# References.net
KiCad netlist of a schematic drawn in Altium Designer
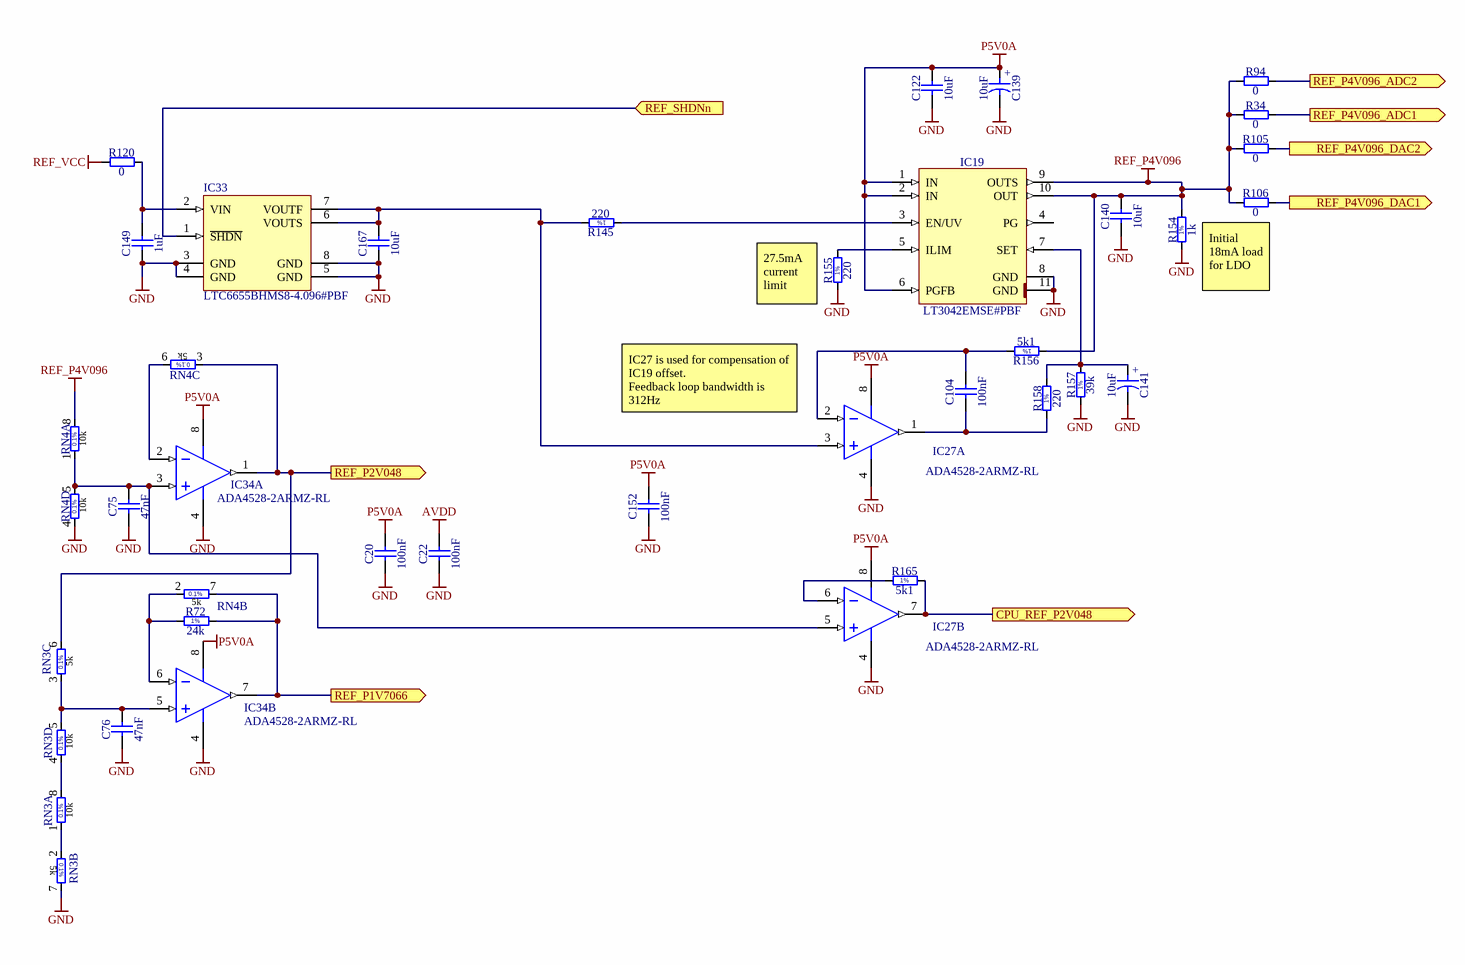
[diagram p0: References.SchDoc]

(export (version "E")
  (design (tool "Eeschema 10.0.6"))
  (components
    (comp (ref "C20")
      (value "100nF")
      (footprint "CAPC1005X55N")
      (description "Non-polarised capacitor")
      (fields
        (field (name "PART NUMBER") "CC0402_100NF_16V_10%_X5R")
        (field (name "VOLTAGE") "16V")
        (field (name "AUTHOR") "CERN DEM JLC")
      )
      (libsource (lib "Capacitors") (part "Capacitor - non polarized"))
    )
    (comp (ref "C22")
      (value "100nF")
      (footprint "CAPC1005X55N")
      (description "Non-polarised capacitor")
      (fields
        (field (name "PART NUMBER") "CC0402_100NF_16V_10%_X5R")
        (field (name "VOLTAGE") "16V")
        (field (name "AUTHOR") "CERN DEM JLC")
      )
      (libsource (lib "Capacitors") (part "Capacitor - non polarized"))
    )
    (comp (ref "C75")
      (value "47nF")
      (footprint "CAPC2012X135N")
      (description "Non-polarised capacitor")
      (fields
        (field (name "PART NUMBER") "CC0805_47NF_25V_5%_C0G")
        (field (name "VOLTAGE") "25V")
        (field (name "AUTHOR") "CERN DEM JLC")
      )
      (libsource (lib "Capacitors") (part "Capacitor - non polarized"))
    )
    (comp (ref "C76")
      (value "47nF")
      (footprint "CAPC2012X135N")
      (description "Non-polarised capacitor")
      (fields
        (field (name "PART NUMBER") "CC0805_47NF_25V_5%_C0G")
        (field (name "VOLTAGE") "25V")
        (field (name "AUTHOR") "CERN DEM JLC")
      )
      (libsource (lib "Capacitors") (part "Capacitor - non polarized"))
    )
    (comp (ref "C104")
      (value "100nF")
      (footprint "CAPC1005X55N")
      (description "Non-polarised capacitor")
      (fields
        (field (name "PART NUMBER") "CC0402_100NF_16V_10%_X5R")
        (field (name "VOLTAGE") "16V")
        (field (name "AUTHOR") "CERN DEM JLC")
      )
      (libsource (lib "Capacitors") (part "Capacitor - non polarized"))
    )
    (comp (ref "C122")
      (value "10uF")
      (footprint "CAPC1608X80N")
      (description "Non-polarised capacitor")
      (fields
        (field (name "PART NUMBER") "CC0603_10UF_10V_10%_X5R")
        (field (name "VOLTAGE") "10V")
        (field (name "AUTHOR") "CERN DEM JLC")
      )
      (libsource (lib "Capacitors") (part "Capacitor - non polarized"))
    )
    (comp (ref "C139")
      (value "10uF")
      (footprint "CAPMP3216X180N")
      (description "Polarised capacitor")
      (fields
        (field (name "PART NUMBER") "CTE3216-18_10UF_16V_20%_AVX_TCJ")
        (field (name "VOLTAGE") "16V")
        (field (name "AUTHOR") "CERN DEM JLC")
      )
      (libsource (lib "Capacitors") (part "Capacitor - polarized"))
    )
    (comp (ref "C140")
      (value "10uF")
      (footprint "CAPC1608X80N")
      (description "Non-polarised capacitor")
      (fields
        (field (name "PART NUMBER") "CC0603_10UF_10V_10%_X5R")
        (field (name "VOLTAGE") "10V")
        (field (name "AUTHOR") "CERN DEM JLC")
      )
      (libsource (lib "Capacitors") (part "Capacitor - non polarized"))
    )
    (comp (ref "C141")
      (value "10uF")
      (footprint "CAPMP3216X180N")
      (description "Polarised capacitor")
      (fields
        (field (name "PART NUMBER") "CTE3216-18_10UF_16V_20%_AVX_TCJ")
        (field (name "VOLTAGE") "16V")
        (field (name "AUTHOR") "CERN DEM JLC")
      )
      (libsource (lib "Capacitors") (part "Capacitor - polarized"))
    )
    (comp (ref "C149")
      (value "1uF")
      (footprint "CAPC1608X87N")
      (description "Non-polarised capacitor")
      (fields
        (field (name "PART NUMBER") "CC0603_1UF_25V_10%_X7R")
        (field (name "VOLTAGE") "25V")
        (field (name "AUTHOR") "CERN DEM JLC")
      )
      (libsource (lib "Capacitors") (part "Capacitor - non polarized"))
    )
    (comp (ref "C152")
      (value "100nF")
      (footprint "CAPC1005X55N")
      (description "Non-polarised capacitor")
      (fields
        (field (name "PART NUMBER") "CC0402_100NF_16V_10%_X5R")
        (field (name "VOLTAGE") "16V")
        (field (name "AUTHOR") "CERN DEM JLC")
      )
      (libsource (lib "Capacitors") (part "Capacitor - non polarized"))
    )
    (comp (ref "C167")
      (value "10uF")
      (footprint "CAPC1608X80N")
      (description "Non-polarised capacitor")
      (fields
        (field (name "PART NUMBER") "CC0603_10UF_10V_10%_X5R")
        (field (name "VOLTAGE") "10V")
        (field (name "AUTHOR") "CERN DEM JLC")
      )
      (libsource (lib "Capacitors") (part "Capacitor - non polarized"))
    )
    (comp (ref "IC19")
      (value "LT3042EMSE#PBF")
      (footprint "SOP50P490X110-11N-R168X198")
      (description "20V, 200mA, Ultralow Noise, Ultrahigh PSRR RF Linear Regulator")
      (fields (field (name "MANUFACTURER") "LINEAR TECHNOLOGY") (field (name "AUTHOR") "CERN DEM MR"))
      (libsource (lib "ICs And Semiconductors") (part "LT3042"))
    )
    (comp (ref "IC27")
      (value "ADA4528-2ARMZ-RL")
      (footprint "ADI-RM-8_N")
      (fields (field (name "GENERIC PART NUMBER") "ADA4528-2") (field (name "MANUFACTURER") "Analog Devices"))
      (libsource (lib "Altium Content Vault") (part "ADI-ADA4000-2-X-8"))
    )
    (comp (ref "IC33")
      (value "LTC6655BHMS8-4.096#PBF")
      (footprint "SOP65P490X110-8N")
      (description "0.25ppm Noise, Low Drift Precision Buffered Voltage Reference")
      (fields (field (name "MANUFACTURER") "LINEAR TECHNOLOGY") (field (name "AUTHOR") "GK"))
      (libsource (lib "LIBRARY_SCH") (part "REF_LTC6655"))
    )
    (comp (ref "IC34")
      (value "ADA4528-2ARMZ-RL")
      (footprint "ADI-RM-8_N")
      (fields (field (name "GENERIC PART NUMBER") "ADA4528-2") (field (name "MANUFACTURER") "Analog Devices"))
      (libsource (lib "Altium Content Vault") (part "ADI-ADA4000-2-X-8"))
    )
    (comp (ref "R34")
      (value "0")
      (footprint "RESC1005X40N")
      (description "Resistor")
      (fields
        (field (name "PART NUMBER") "R0402_0R_JUMPER")
        (field (name "MANUFACTURER") "GENERIC")
        (field (name "AUTHOR") "CERN DEM JLC")
      )
      (libsource (lib "Resistors") (part "Resistor"))
    )
    (comp (ref "R72")
      (value "24k")
      (footprint "RESC1608X55N")
      (description "Resistor - 1%")
      (fields
        (field (name "PART NUMBER") "R0603_24K_1%_0.1W_100PPM")
        (field (name "POWER") "0.1W")
        (field (name "AUTHOR") "CERN DEM JLC")
      )
      (libsource (lib "Resistors") (part "Resistor - 1%"))
    )
    (comp (ref "R94")
      (value "0")
      (footprint "RESC1005X40N")
      (description "Resistor")
      (fields
        (field (name "PART NUMBER") "R0402_0R_JUMPER")
        (field (name "MANUFACTURER") "GENERIC")
        (field (name "AUTHOR") "CERN DEM JLC")
      )
      (libsource (lib "Resistors") (part "Resistor"))
    )
    (comp (ref "R105")
      (value "0")
      (footprint "RESC1005X40N")
      (description "Resistor")
      (fields
        (field (name "PART NUMBER") "R0402_0R_JUMPER")
        (field (name "MANUFACTURER") "GENERIC")
        (field (name "AUTHOR") "CERN DEM JLC")
      )
      (libsource (lib "Resistors") (part "Resistor"))
    )
    (comp (ref "R106")
      (value "0")
      (footprint "RESC1005X40N")
      (description "Resistor")
      (fields
        (field (name "PART NUMBER") "R0402_0R_JUMPER")
        (field (name "MANUFACTURER") "GENERIC")
        (field (name "AUTHOR") "CERN DEM JLC")
      )
      (libsource (lib "Resistors") (part "Resistor"))
    )
    (comp (ref "R120")
      (value "0")
      (footprint "RESC1005X40N")
      (description "Resistor")
      (fields
        (field (name "PART NUMBER") "R0402_0R_JUMPER")
        (field (name "MANUFACTURER") "GENERIC")
        (field (name "AUTHOR") "CERN DEM JLC")
      )
      (libsource (lib "Resistors") (part "Resistor"))
    )
    (comp (ref "R145")
      (value "220")
      (footprint "RESC1005X40N")
      (description "Resistor - 1%")
      (fields
        (field (name "PART NUMBER") "R0402_220R_1%_0.0625W_100PPM")
        (field (name "POWER") "0.0625W")
        (field (name "AUTHOR") "CERN DEM JLC")
      )
      (libsource (lib "Resistors") (part "Resistor - 1%"))
    )
    (comp (ref "R154")
      (value "1k")
      (footprint "RESC1005X40N")
      (description "Resistor - 1%")
      (fields
        (field (name "PART NUMBER") "R0402_1K_1%_0.0625W_100PPM")
        (field (name "POWER") "0.0625W")
        (field (name "AUTHOR") "CERN DEM JLC")
      )
      (libsource (lib "Resistors") (part "Resistor - 1%"))
    )
    (comp (ref "R155")
      (value "220")
      (footprint "RESC1005X40N")
      (description "Resistor - 1%")
      (fields
        (field (name "PART NUMBER") "R0402_220R_1%_0.0625W_100PPM")
        (field (name "POWER") "0.0625W")
        (field (name "AUTHOR") "CERN DEM JLC")
      )
      (libsource (lib "Resistors") (part "Resistor - 1%"))
    )
    (comp (ref "R156")
      (value "5k1")
      (footprint "RESC1005X40N")
      (description "Resistor - 1%")
      (fields
        (field (name "PART NUMBER") "R0402_5K1_1%_0.0625W_100PPM")
        (field (name "POWER") "0.0625W")
        (field (name "AUTHOR") "CERN DEM JLC")
      )
      (libsource (lib "Resistors") (part "Resistor - 1%"))
    )
    (comp (ref "R157")
      (value "39k")
      (footprint "RESC1608X55N")
      (description "Resistor - 1%")
      (fields
        (field (name "PART NUMBER") "R0603_39K_1%_0.1W_100PPM")
        (field (name "POWER") "0.1W")
        (field (name "AUTHOR") "CERN DEM JLC")
      )
      (libsource (lib "Resistors") (part "Resistor - 1%"))
    )
    (comp (ref "R158")
      (value "220")
      (footprint "RESC1005X40N")
      (description "Resistor - 1%")
      (fields
        (field (name "PART NUMBER") "R0402_220R_1%_0.0625W_100PPM")
        (field (name "POWER") "0.0625W")
        (field (name "AUTHOR") "CERN DEM JLC")
      )
      (libsource (lib "Resistors") (part "Resistor - 1%"))
    )
    (comp (ref "R165")
      (value "5k1")
      (footprint "RESC1005X40N")
      (description "Resistor - 1%")
      (fields
        (field (name "PART NUMBER") "R0402_5K1_1%_0.0625W_100PPM")
        (field (name "POWER") "0.0625W")
        (field (name "AUTHOR") "CERN DEM JLC")
      )
      (libsource (lib "Resistors") (part "Resistor - 1%"))
    )
    (comp (ref "RN3")
      (value "10k 5K 5K 10K")
      (footprint "SOIC127P600X175-8N")
      (description "DIL8 Resistor Network 4 Resistors 10k-5k-5k-10k 0.1%")
      (fields
        (field (name "PART NUMBER") "RN_10K_5K_VISHAY_AORN2-1AT3")
        (field (name "POWER") "4x0.1W")
        (field (name "AUTHOR") "CERN DEM JLC")
      )
      (libsource (lib "Resistors") (part "RN DIL8_4xR_10k-5k-5k-10k_0.1%"))
    )
    (comp (ref "RN4")
      (value "10k 5K 5K 10K")
      (footprint "SOIC127P600X175-8N")
      (description "DIL8 Resistor Network 4 Resistors 10k-5k-5k-10k 0.1%")
      (fields
        (field (name "PART NUMBER") "RN_10K_5K_VISHAY_AORN2-1AT3")
        (field (name "POWER") "4x0.1W")
        (field (name "AUTHOR") "CERN DEM JLC")
      )
      (libsource (lib "Resistors") (part "RN DIL8_4xR_10k-5k-5k-10k_0.1%"))
    )
  )
  (nets
    (net (code "1") (name "/CPU_REF_P2V048") (class "Default")
      (node (ref "IC27") (pin "7") (pinfunction "OUT_B_7") (pintype "output"))
      (node (ref "R165") (pin "2") (pinfunction "2_2") (pintype "passive"))
    )
    (net (code "2") (name "/REF_P1V7066") (class "Default")
      (node (ref "IC34") (pin "7") (pinfunction "OUT_B_7") (pintype "output"))
      (node (ref "R72") (pin "2") (pinfunction "2_2") (pintype "passive"))
      (node (ref "RN4") (pin "7") (pinfunction "7_7") (pintype "passive"))
    )
    (net (code "3") (name "/REF_P2V048") (class "Default")
      (node (ref "IC34") (pin "1") (pinfunction "OUT_A_1") (pintype "output"))
      (node (ref "RN3") (pin "6") (pinfunction "6_6") (pintype "passive"))
      (node (ref "RN4") (pin "3") (pinfunction "3_3") (pintype "passive"))
    )
    (net (code "4") (name "/REF_P4V096_ADC1") (class "Default")
      (node (ref "R34") (pin "2") (pinfunction "2_2") (pintype "passive"))
    )
    (net (code "5") (name "/REF_P4V096_ADC2") (class "Default")
      (node (ref "R94") (pin "2") (pinfunction "2_2") (pintype "passive"))
    )
    (net (code "6") (name "/REF_P4V096_DAC1") (class "Default")
      (node (ref "R106") (pin "2") (pinfunction "2_2") (pintype "passive"))
    )
    (net (code "7") (name "/REF_P4V096_DAC2") (class "Default")
      (node (ref "R105") (pin "2") (pinfunction "2_2") (pintype "passive"))
    )
    (net (code "8") (name "/REF_SHDNn") (class "Default")
      (node (ref "IC33") (pin "1") (pinfunction "~{SHDN}_1") (pintype "input"))
    )
    (net (code "9") (name "AVDD") (class "Default")
      (node (ref "C22") (pin "2") (pinfunction "2_2") (pintype "passive"))
    )
    (net (code "10") (name "GND") (class "Default")
      (node (ref "C122") (pin "1") (pinfunction "1_1") (pintype "passive"))
      (node (ref "C139") (pin "2") (pinfunction "2_2") (pintype "passive"))
      (node (ref "C140") (pin "1") (pinfunction "1_1") (pintype "passive"))
      (node (ref "C141") (pin "2") (pinfunction "2_2") (pintype "passive"))
      (node (ref "C149") (pin "1") (pinfunction "1_1") (pintype "passive"))
      (node (ref "C152") (pin "1") (pinfunction "1_1") (pintype "passive"))
      (node (ref "C167") (pin "1") (pinfunction "1_1") (pintype "passive"))
      (node (ref "C20") (pin "1") (pinfunction "1_1") (pintype "passive"))
      (node (ref "C22") (pin "1") (pinfunction "1_1") (pintype "passive"))
      (node (ref "C75") (pin "1") (pinfunction "1_1") (pintype "passive"))
      (node (ref "C76") (pin "1") (pinfunction "1_1") (pintype "passive"))
      (node (ref "IC19") (pin "11") (pinfunction "GND_11") (pintype "power_in"))
      (node (ref "IC19") (pin "8") (pinfunction "GND_8") (pintype "power_in"))
      (node (ref "IC27") (pin "4") (pinfunction "-V_4") (pintype "power_in"))
      (node (ref "IC33") (pin "3") (pinfunction "GND_3") (pintype "power_in"))
      (node (ref "IC33") (pin "4") (pinfunction "GND_4") (pintype "power_in"))
      (node (ref "IC33") (pin "5") (pinfunction "GND_5") (pintype "power_in"))
      (node (ref "IC33") (pin "8") (pinfunction "GND_8") (pintype "power_in"))
      (node (ref "IC34") (pin "4") (pinfunction "-V_4") (pintype "power_in"))
      (node (ref "R154") (pin "1") (pinfunction "1_1") (pintype "passive"))
      (node (ref "R155") (pin "1") (pinfunction "1_1") (pintype "passive"))
      (node (ref "R157") (pin "1") (pinfunction "1_1") (pintype "passive"))
      (node (ref "RN3") (pin "7") (pinfunction "7_7") (pintype "passive"))
      (node (ref "RN4") (pin "4") (pinfunction "4_4") (pintype "passive"))
    )
    (net (code "11") (name "Net-(IC19-EN{slash}UV)") (class "Default")
      (node (ref "IC19") (pin "3") (pinfunction "EN/UV_3") (pintype "input"))
      (node (ref "R145") (pin "1") (pinfunction "1_1") (pintype "passive"))
    )
    (net (code "12") (name "Net-(IC19-ILIM)") (class "Default")
      (node (ref "IC19") (pin "5") (pinfunction "ILIM_5") (pintype "input"))
      (node (ref "R155") (pin "2") (pinfunction "2_2") (pintype "passive"))
    )
    (net (code "13") (name "Net-(IC19-SET)") (class "Default")
      (node (ref "C141") (pin "1") (pinfunction "1_1") (pintype "passive"))
      (node (ref "IC19") (pin "7") (pinfunction "SET_7") (pintype "input"))
      (node (ref "R157") (pin "2") (pinfunction "2_2") (pintype "passive"))
      (node (ref "R158") (pin "2") (pinfunction "2_2") (pintype "passive"))
    )
    (net (code "14") (name "Net-(IC27A-+IN_A)") (class "Default")
      (node (ref "C167") (pin "2") (pinfunction "2_2") (pintype "passive"))
      (node (ref "IC27") (pin "3") (pinfunction "+IN_A_3") (pintype "input"))
      (node (ref "IC33") (pin "6") (pinfunction "VOUTS_6") (pintype "power_in"))
      (node (ref "IC33") (pin "7") (pinfunction "VOUTF_7") (pintype "power_in"))
      (node (ref "R145") (pin "2") (pinfunction "2_2") (pintype "passive"))
    )
    (net (code "15") (name "Net-(IC27A--IN_A)") (class "Default")
      (node (ref "C104") (pin "2") (pinfunction "2_2") (pintype "passive"))
      (node (ref "IC27") (pin "2") (pinfunction "-IN_A_2") (pintype "input"))
      (node (ref "R156") (pin "2") (pinfunction "2_2") (pintype "passive"))
    )
    (net (code "16") (name "Net-(IC27A-OUT_A)") (class "Default")
      (node (ref "C104") (pin "1") (pinfunction "1_1") (pintype "passive"))
      (node (ref "IC27") (pin "1") (pinfunction "OUT_A_1") (pintype "output"))
      (node (ref "R158") (pin "1") (pinfunction "1_1") (pintype "passive"))
    )
    (net (code "17") (name "Net-(IC27B-+IN_B)") (class "Default")
      (node (ref "C75") (pin "2") (pinfunction "2_2") (pintype "passive"))
      (node (ref "IC27") (pin "5") (pinfunction "+IN_B_5") (pintype "input"))
      (node (ref "IC34") (pin "3") (pinfunction "+IN_A_3") (pintype "input"))
      (node (ref "RN4") (pin "1") (pinfunction "1_1") (pintype "passive"))
      (node (ref "RN4") (pin "5") (pinfunction "5_5") (pintype "passive"))
    )
    (net (code "18") (name "Net-(IC27B--IN_B)") (class "Default")
      (node (ref "IC27") (pin "6") (pinfunction "-IN_B_6") (pintype "input"))
      (node (ref "R165") (pin "1") (pinfunction "1_1") (pintype "passive"))
    )
    (net (code "19") (name "Net-(IC33-VIN)") (class "Default")
      (node (ref "C149") (pin "2") (pinfunction "2_2") (pintype "passive"))
      (node (ref "IC33") (pin "2") (pinfunction "VIN_2") (pintype "input"))
      (node (ref "R120") (pin "2") (pinfunction "2_2") (pintype "passive"))
    )
    (net (code "20") (name "Net-(IC34A--IN_A)") (class "Default")
      (node (ref "IC34") (pin "2") (pinfunction "-IN_A_2") (pintype "input"))
      (node (ref "RN4") (pin "6") (pinfunction "6_6") (pintype "passive"))
    )
    (net (code "21") (name "Net-(IC34B-+IN_B)") (class "Default")
      (node (ref "C76") (pin "2") (pinfunction "2_2") (pintype "passive"))
      (node (ref "IC34") (pin "5") (pinfunction "+IN_B_5") (pintype "input"))
      (node (ref "RN3") (pin "3") (pinfunction "3_3") (pintype "passive"))
      (node (ref "RN3") (pin "5") (pinfunction "5_5") (pintype "passive"))
    )
    (net (code "22") (name "Net-(IC34B--IN_B)") (class "Default")
      (node (ref "IC34") (pin "6") (pinfunction "-IN_B_6") (pintype "input"))
      (node (ref "R72") (pin "1") (pinfunction "1_1") (pintype "passive"))
      (node (ref "RN4") (pin "2") (pinfunction "2_2") (pintype "passive"))
    )
    (net (code "23") (name "Net-(RN3-Pad1)") (class "Default")
      (node (ref "RN3") (pin "1") (pinfunction "1_1") (pintype "passive"))
      (node (ref "RN3") (pin "2") (pinfunction "2_2") (pintype "passive"))
    )
    (net (code "24") (name "Net-(RN3-Pad4)") (class "Default")
      (node (ref "RN3") (pin "4") (pinfunction "4_4") (pintype "passive"))
      (node (ref "RN3") (pin "8") (pinfunction "8_8") (pintype "passive"))
    )
    (net (code "25") (name "P5V0A") (class "Default")
      (node (ref "C122") (pin "2") (pinfunction "2_2") (pintype "passive"))
      (node (ref "C139") (pin "1") (pinfunction "1_1") (pintype "passive"))
      (node (ref "C152") (pin "2") (pinfunction "2_2") (pintype "passive"))
      (node (ref "C20") (pin "2") (pinfunction "2_2") (pintype "passive"))
      (node (ref "IC19") (pin "1") (pinfunction "IN_1") (pintype "input"))
      (node (ref "IC19") (pin "2") (pinfunction "IN_2") (pintype "input"))
      (node (ref "IC19") (pin "6") (pinfunction "PGFB_6") (pintype "input"))
      (node (ref "IC27") (pin "8") (pinfunction "+V_8") (pintype "power_in"))
      (node (ref "IC34") (pin "8") (pinfunction "+V_8") (pintype "power_in"))
    )
    (net (code "26") (name "REF_P4V096") (class "Default")
      (node (ref "C140") (pin "2") (pinfunction "2_2") (pintype "passive"))
      (node (ref "IC19") (pin "10") (pinfunction "OUT_10") (pintype "output"))
      (node (ref "IC19") (pin "9") (pinfunction "OUTS_9") (pintype "output"))
      (node (ref "R105") (pin "1") (pinfunction "1_1") (pintype "passive"))
      (node (ref "R106") (pin "1") (pinfunction "1_1") (pintype "passive"))
      (node (ref "R154") (pin "2") (pinfunction "2_2") (pintype "passive"))
      (node (ref "R156") (pin "1") (pinfunction "1_1") (pintype "passive"))
      (node (ref "R34") (pin "1") (pinfunction "1_1") (pintype "passive"))
      (node (ref "R94") (pin "1") (pinfunction "1_1") (pintype "passive"))
      (node (ref "RN4") (pin "8") (pinfunction "8_8") (pintype "passive"))
    )
    (net (code "27") (name "REF_VCC") (class "Default")
      (node (ref "R120") (pin "1") (pinfunction "1_1") (pintype "passive"))
    )
    (net (code "28") (name "unconnected-(IC19-PG-Pad4)") (class "Default")
      (node (ref "IC19") (pin "4") (pinfunction "PG_4") (pintype "output"))
    )
  )
)
